# MicroSD.net
KiCad netlist of a schematic drawn in EAGLE
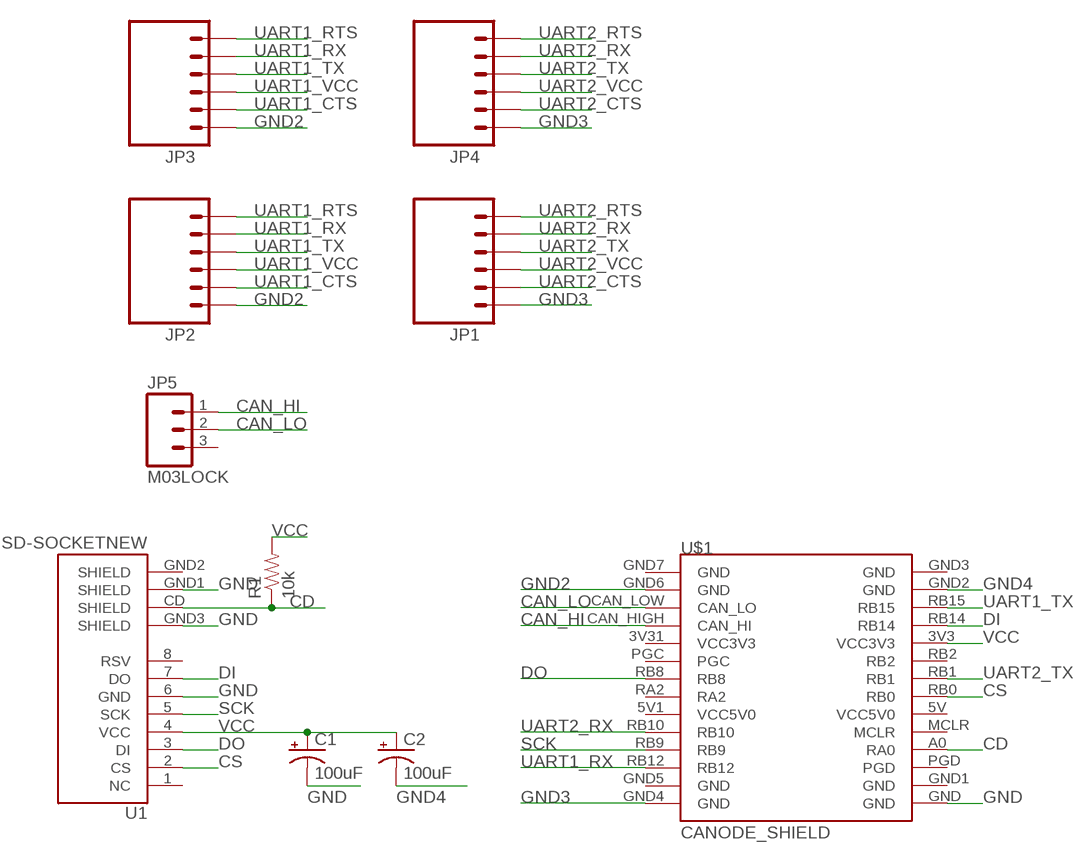
[diagram p0: schematic, sheet 1]

(export (version "E")
  (design (tool "Eeschema 10.0.6"))
  (components
    (comp (ref "C1")
      (value "100uF")
      (footprint "eagle-import:CPOL-RADIAL-100UF-25V")
      (libsource (lib "eagle-import") (part "CAP_POLPTH1"))
    )
    (comp (ref "C2")
      (value "100uF")
      (footprint "eagle-import:CPOL-RADIAL-100UF-25V")
      (libsource (lib "eagle-import") (part "CAP_POLPTH1"))
    )
    (comp (ref "JP1")
      (value "M06LOCK")
      (footprint "eagle-import:1X06_LOCK")
      (libsource (lib "eagle-import") (part "M06LOCK"))
    )
    (comp (ref "JP2")
      (value "M06LOCK")
      (footprint "eagle-import:1X06_LOCK")
      (libsource (lib "eagle-import") (part "M06LOCK"))
    )
    (comp (ref "JP3")
      (value "M06LOCK")
      (footprint "eagle-import:1X06_LOCK")
      (libsource (lib "eagle-import") (part "M06LOCK"))
    )
    (comp (ref "JP4")
      (value "M06LOCK")
      (footprint "eagle-import:1X06_LOCK")
      (libsource (lib "eagle-import") (part "M06LOCK"))
    )
    (comp (ref "JP5")
      (value "M03LOCK")
      (footprint "eagle-import:1X03_LOCK")
      (libsource (lib "eagle-import") (part "M03LOCK"))
    )
    (comp (ref "R1")
      (value "10k")
      (footprint "eagle-import:0805")
      (libsource (lib "eagle-import") (part "RESISTOR0805-RES"))
    )
    (comp (ref "U$1")
      (value "CANODE_SHIELD")
      (footprint "eagle-import:CANODE_SHIELD")
      (libsource (lib "eagle-import") (part "CANODE_SHIELD"))
    )
    (comp (ref "U1")
      (value "USD-SOCKETNEW")
      (footprint "eagle-import:MICRO-SD-SOCKET-PP")
      (libsource (lib "eagle-import") (part "USD-SOCKETNEW"))
    )
  )
  (nets
    (net (code "1") (name "/CAN_HI") (class "Default")
      (node (ref "JP5") (pin "1") (pinfunction "1_1") (pintype "passive"))
      (node (ref "U$1") (pin "CAN_HIGH") (pinfunction "CAN_HI_CAN_HIGH") (pintype "bidirectional"))
    )
    (net (code "2") (name "/CAN_LO") (class "Default")
      (node (ref "JP5") (pin "2") (pinfunction "2_2") (pintype "passive"))
      (node (ref "U$1") (pin "CAN_LOW") (pinfunction "CAN_LO_CAN_LOW") (pintype "bidirectional"))
    )
    (net (code "3") (name "/CD") (class "Default")
      (node (ref "R1") (pin "1") (pinfunction "1_1") (pintype "passive"))
      (node (ref "U$1") (pin "A0") (pinfunction "RA0_A0") (pintype "bidirectional"))
      (node (ref "U1") (pin "CD") (pinfunction "SHIELD_CD") (pintype "bidirectional"))
    )
    (net (code "4") (name "/CS") (class "Default")
      (node (ref "U$1") (pin "RB0") (pinfunction "RB0_RB0") (pintype "bidirectional"))
      (node (ref "U1") (pin "2") (pinfunction "CS_2") (pintype "bidirectional"))
    )
    (net (code "5") (name "/DI") (class "Default")
      (node (ref "U$1") (pin "RB14") (pinfunction "RB14_RB14") (pintype "bidirectional"))
      (node (ref "U1") (pin "7") (pinfunction "DO_7") (pintype "bidirectional"))
    )
    (net (code "6") (name "/DO") (class "Default")
      (node (ref "U$1") (pin "RB8") (pinfunction "RB8_RB8") (pintype "bidirectional"))
      (node (ref "U1") (pin "3") (pinfunction "DI_3") (pintype "bidirectional"))
    )
    (net (code "7") (name "/GND") (class "Default")
      (node (ref "C1") (pin "2") (pinfunction "-_2") (pintype "passive"))
      (node (ref "U$1") (pin "GND") (pinfunction "GND_GND") (pintype "bidirectional"))
      (node (ref "U1") (pin "6") (pinfunction "GND_6") (pintype "bidirectional"))
      (node (ref "U1") (pin "GND1") (pinfunction "SHIELD_GND1") (pintype "bidirectional"))
      (node (ref "U1") (pin "GND3") (pinfunction "SHIELD_GND3") (pintype "bidirectional"))
    )
    (net (code "8") (name "/GND2") (class "Default")
      (node (ref "JP2") (pin "1") (pinfunction "1_1") (pintype "passive"))
      (node (ref "JP3") (pin "1") (pinfunction "1_1") (pintype "passive"))
      (node (ref "U$1") (pin "GND6") (pinfunction "GND_GND6") (pintype "bidirectional"))
    )
    (net (code "9") (name "/GND3") (class "Default")
      (node (ref "JP1") (pin "1") (pinfunction "1_1") (pintype "passive"))
      (node (ref "JP4") (pin "1") (pinfunction "1_1") (pintype "passive"))
      (node (ref "U$1") (pin "GND4") (pinfunction "GND_GND4") (pintype "bidirectional"))
    )
    (net (code "10") (name "/GND4") (class "Default")
      (node (ref "C2") (pin "2") (pinfunction "-_2") (pintype "passive"))
      (node (ref "U$1") (pin "GND2") (pinfunction "GND_GND2") (pintype "bidirectional"))
    )
    (net (code "11") (name "/SCK") (class "Default")
      (node (ref "U$1") (pin "RB9") (pinfunction "RB9_RB9") (pintype "bidirectional"))
      (node (ref "U1") (pin "5") (pinfunction "SCK_5") (pintype "bidirectional"))
    )
    (net (code "12") (name "/UART1_CTS") (class "Default")
      (node (ref "JP2") (pin "2") (pinfunction "2_2") (pintype "passive"))
      (node (ref "JP3") (pin "2") (pinfunction "2_2") (pintype "passive"))
    )
    (net (code "13") (name "/UART1_RTS") (class "Default")
      (node (ref "JP2") (pin "6") (pinfunction "6_6") (pintype "passive"))
      (node (ref "JP3") (pin "6") (pinfunction "6_6") (pintype "passive"))
    )
    (net (code "14") (name "/UART1_RX") (class "Default")
      (node (ref "JP2") (pin "5") (pinfunction "5_5") (pintype "passive"))
      (node (ref "JP3") (pin "5") (pinfunction "5_5") (pintype "passive"))
      (node (ref "U$1") (pin "RB12") (pinfunction "RB12_RB12") (pintype "bidirectional"))
    )
    (net (code "15") (name "/UART1_TX") (class "Default")
      (node (ref "JP2") (pin "4") (pinfunction "4_4") (pintype "passive"))
      (node (ref "JP3") (pin "4") (pinfunction "4_4") (pintype "passive"))
      (node (ref "U$1") (pin "RB15") (pinfunction "RB15_RB15") (pintype "bidirectional"))
    )
    (net (code "16") (name "/UART1_VCC") (class "Default")
      (node (ref "JP2") (pin "3") (pinfunction "3_3") (pintype "passive"))
      (node (ref "JP3") (pin "3") (pinfunction "3_3") (pintype "passive"))
    )
    (net (code "17") (name "/UART2_CTS") (class "Default")
      (node (ref "JP1") (pin "2") (pinfunction "2_2") (pintype "passive"))
      (node (ref "JP4") (pin "2") (pinfunction "2_2") (pintype "passive"))
    )
    (net (code "18") (name "/UART2_RTS") (class "Default")
      (node (ref "JP1") (pin "6") (pinfunction "6_6") (pintype "passive"))
      (node (ref "JP4") (pin "6") (pinfunction "6_6") (pintype "passive"))
    )
    (net (code "19") (name "/UART2_RX") (class "Default")
      (node (ref "JP1") (pin "5") (pinfunction "5_5") (pintype "passive"))
      (node (ref "JP4") (pin "5") (pinfunction "5_5") (pintype "passive"))
      (node (ref "U$1") (pin "RB10") (pinfunction "RB10_RB10") (pintype "bidirectional"))
    )
    (net (code "20") (name "/UART2_TX") (class "Default")
      (node (ref "JP1") (pin "4") (pinfunction "4_4") (pintype "passive"))
      (node (ref "JP4") (pin "4") (pinfunction "4_4") (pintype "passive"))
      (node (ref "U$1") (pin "RB1") (pinfunction "RB1_RB1") (pintype "bidirectional"))
    )
    (net (code "21") (name "/UART2_VCC") (class "Default")
      (node (ref "JP1") (pin "3") (pinfunction "3_3") (pintype "passive"))
      (node (ref "JP4") (pin "3") (pinfunction "3_3") (pintype "passive"))
    )
    (net (code "22") (name "/VCC") (class "Default")
      (node (ref "C1") (pin "1") (pinfunction "+_1") (pintype "passive"))
      (node (ref "C2") (pin "1") (pinfunction "+_1") (pintype "passive"))
      (node (ref "R1") (pin "2") (pinfunction "2_2") (pintype "passive"))
      (node (ref "U$1") (pin "3V3") (pinfunction "VCC3V3_3V3") (pintype "bidirectional"))
      (node (ref "U1") (pin "4") (pinfunction "VCC_4") (pintype "bidirectional"))
    )
    (net (code "23") (name "unconnected-(JP5-Pad3)") (class "Default")
      (node (ref "JP5") (pin "3") (pinfunction "3_3") (pintype "passive"))
    )
    (net (code "24") (name "unconnected-(U$1-GND-PadGND1)") (class "Default")
      (node (ref "U$1") (pin "GND1") (pinfunction "GND_GND1") (pintype "bidirectional"))
    )
    (net (code "25") (name "unconnected-(U$1-GND-PadGND3)") (class "Default")
      (node (ref "U$1") (pin "GND3") (pinfunction "GND_GND3") (pintype "bidirectional"))
    )
    (net (code "26") (name "unconnected-(U$1-GND-PadGND5)") (class "Default")
      (node (ref "U$1") (pin "GND5") (pinfunction "GND_GND5") (pintype "bidirectional"))
    )
    (net (code "27") (name "unconnected-(U$1-GND-PadGND7)") (class "Default")
      (node (ref "U$1") (pin "GND7") (pinfunction "GND_GND7") (pintype "bidirectional"))
    )
    (net (code "28") (name "unconnected-(U$1-PadMCLR)") (class "Default")
      (node (ref "U$1") (pin "MCLR") (pinfunction "MCLR_MCLR") (pintype "bidirectional"))
    )
    (net (code "29") (name "unconnected-(U$1-PadPGC)") (class "Default")
      (node (ref "U$1") (pin "PGC") (pinfunction "PGC_PGC") (pintype "bidirectional"))
    )
    (net (code "30") (name "unconnected-(U$1-PadPGD)") (class "Default")
      (node (ref "U$1") (pin "PGD") (pinfunction "PGD_PGD") (pintype "bidirectional"))
    )
    (net (code "31") (name "unconnected-(U$1-PadRA2)") (class "Default")
      (node (ref "U$1") (pin "RA2") (pinfunction "RA2_RA2") (pintype "bidirectional"))
    )
    (net (code "32") (name "unconnected-(U$1-PadRB2)") (class "Default")
      (node (ref "U$1") (pin "RB2") (pinfunction "RB2_RB2") (pintype "bidirectional"))
    )
    (net (code "33") (name "unconnected-(U$1-VCC3V3-Pad3V31)") (class "Default")
      (node (ref "U$1") (pin "3V31") (pinfunction "VCC3V3_3V31") (pintype "bidirectional"))
    )
    (net (code "34") (name "unconnected-(U$1-VCC5V0-Pad5V)") (class "Default")
      (node (ref "U$1") (pin "5V") (pinfunction "VCC5V0_5V") (pintype "bidirectional"))
    )
    (net (code "35") (name "unconnected-(U$1-VCC5V0-Pad5V1)") (class "Default")
      (node (ref "U$1") (pin "5V1") (pinfunction "VCC5V0_5V1") (pintype "bidirectional"))
    )
    (net (code "36") (name "unconnected-(U1-NC-Pad1)") (class "Default")
      (node (ref "U1") (pin "1") (pinfunction "NC_1") (pintype "bidirectional"))
    )
    (net (code "37") (name "unconnected-(U1-RSV-Pad8)") (class "Default")
      (node (ref "U1") (pin "8") (pinfunction "RSV_8") (pintype "bidirectional"))
    )
    (net (code "38") (name "unconnected-(U1-SHIELD-PadGND2)") (class "Default")
      (node (ref "U1") (pin "GND2") (pinfunction "SHIELD_GND2") (pintype "bidirectional"))
    )
  )
)
